# ATMega328PCBBoard.net
KiCad netlist of a schematic drawn in EAGLE
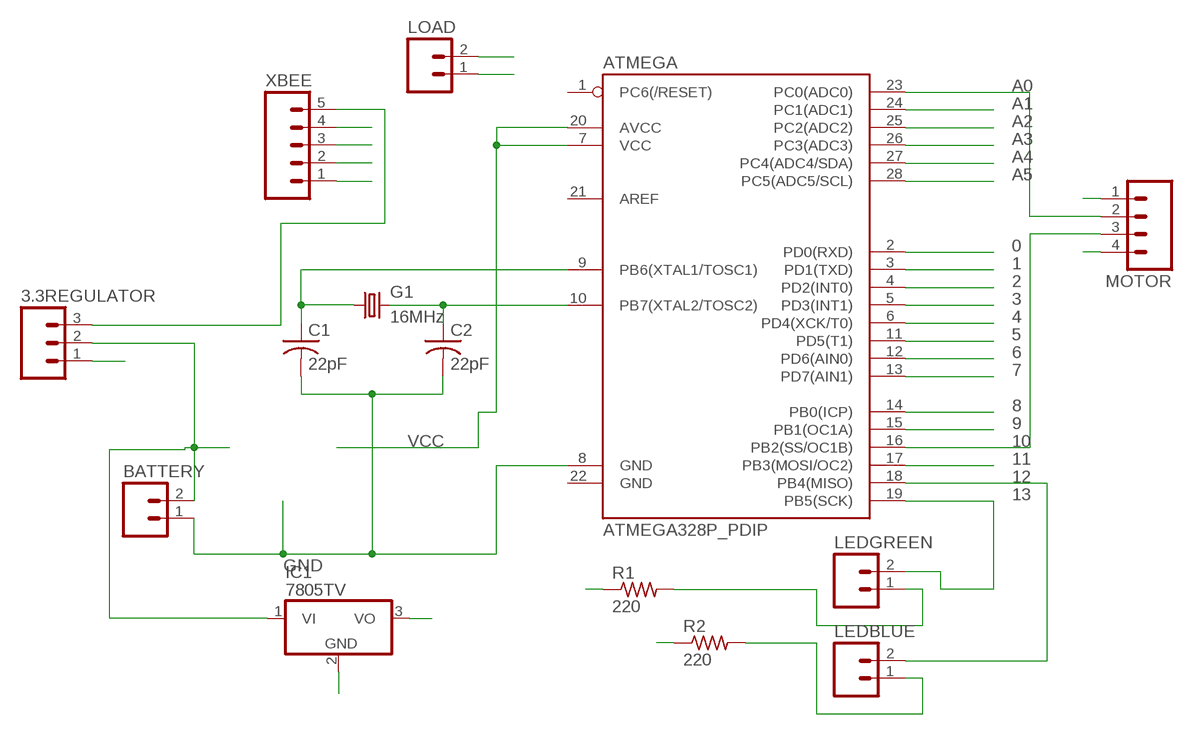
[diagram p0: schematic, sheet 1]

(export (version "E")
  (design (tool "Eeschema 10.0.6"))
  (components
    (comp (ref "3.3REGULATOR")
      (value "M03JST-PTH-VERT")
      (footprint "eagle-import:JST-3-PTH-VERT")
      (libsource (lib "eagle-import") (part "M03JST-PTH-VERT"))
    )
    (comp (ref "ATMEGA")
      (value "ATMEGA328P_PDIP")
      (footprint "eagle-import:DIL28-3")
      (libsource (lib "eagle-import") (part "ATMEGA328P_PDIP"))
    )
    (comp (ref "BATTERY")
      (value "M02JST-PTH-VERT")
      (footprint "eagle-import:JST-2-PTH-VERT")
      (libsource (lib "eagle-import") (part "M02JST-PTH-VERT"))
    )
    (comp (ref "C1")
      (value "22pF")
      (footprint "eagle-import:C050-025X075")
      (libsource (lib "eagle-import") (part "C-US050-025X075"))
    )
    (comp (ref "C2")
      (value "22pF")
      (footprint "eagle-import:C050-025X075")
      (libsource (lib "eagle-import") (part "C-US050-025X075"))
    )
    (comp (ref "G1")
      (value "16MHz")
      (footprint "eagle-import:HC49US")
      (libsource (lib "eagle-import") (part "CRYSTALHC49US"))
    )
    (comp (ref "IC1")
      (value "7805TV")
      (footprint "eagle-import:TO220V")
      (libsource (lib "eagle-import") (part "78TV05"))
    )
    (comp (ref "LEDBLUE")
      (value "M02JST-PTH-VERT")
      (footprint "eagle-import:JST-2-PTH-VERT")
      (libsource (lib "eagle-import") (part "M02JST-PTH-VERT"))
    )
    (comp (ref "LEDGREEN")
      (value "M02JST-PTH-VERT")
      (footprint "eagle-import:JST-2-PTH-VERT")
      (libsource (lib "eagle-import") (part "M02JST-PTH-VERT"))
    )
    (comp (ref "LOAD")
      (value "M02JST-PTH-VERT")
      (footprint "eagle-import:JST-2-PTH-VERT")
      (libsource (lib "eagle-import") (part "M02JST-PTH-VERT"))
    )
    (comp (ref "MOTOR")
      (value "M04JST")
      (footprint "eagle-import:1X04-1.5MM_JST")
      (libsource (lib "eagle-import") (part "M04JST"))
    )
    (comp (ref "R1")
      (value "220")
      (footprint "eagle-import:0207_2V")
      (libsource (lib "eagle-import") (part "R-US_0207/2V"))
    )
    (comp (ref "R2")
      (value "220")
      (footprint "eagle-import:0207_2V")
      (libsource (lib "eagle-import") (part "R-US_0207/2V"))
    )
    (comp (ref "XBEE")
      (value "M05JST-VERT")
      (footprint "eagle-import:JST-5-PTH-VERT")
      (libsource (lib "eagle-import") (part "M05JST-VERT"))
    )
  )
  (nets
    (net (code "1") (name "/0") (class "Default")
      (node (ref "ATMEGA") (pin "2") (pinfunction "PD0(RXD)_2") (pintype "bidirectional"))
      (node (ref "LOAD") (pin "1") (pinfunction "1_1") (pintype "passive"))
      (node (ref "XBEE") (pin "4") (pinfunction "4_4") (pintype "passive"))
    )
    (net (code "2") (name "/1") (class "Default")
      (node (ref "ATMEGA") (pin "3") (pinfunction "PD1(TXD)_3") (pintype "bidirectional"))
      (node (ref "LOAD") (pin "2") (pinfunction "2_2") (pintype "passive"))
      (node (ref "XBEE") (pin "3") (pinfunction "3_3") (pintype "passive"))
    )
    (net (code "3") (name "/7") (class "Default")
      (node (ref "ATMEGA") (pin "13") (pinfunction "PD7(AIN1)_13") (pintype "bidirectional"))
      (node (ref "XBEE") (pin "1") (pinfunction "1_1") (pintype "passive"))
    )
    (net (code "4") (name "/GND") (class "Default")
      (node (ref "3.3REGULATOR") (pin "1") (pinfunction "1_1") (pintype "passive"))
      (node (ref "ATMEGA") (pin "8") (pinfunction "GND_8") (pintype "bidirectional"))
      (node (ref "BATTERY") (pin "1") (pinfunction "1_1") (pintype "passive"))
      (node (ref "C1") (pin "2") (pinfunction "2_2") (pintype "passive"))
      (node (ref "C2") (pin "2") (pinfunction "2_2") (pintype "passive"))
      (node (ref "IC1") (pin "2") (pinfunction "GND_2") (pintype "passive"))
      (node (ref "MOTOR") (pin "4") (pinfunction "4_4") (pintype "passive"))
      (node (ref "R1") (pin "1") (pinfunction "1_1") (pintype "passive"))
      (node (ref "R2") (pin "1") (pinfunction "1_1") (pintype "passive"))
      (node (ref "XBEE") (pin "2") (pinfunction "2_2") (pintype "passive"))
    )
    (net (code "5") (name "/VCC") (class "Default")
      (node (ref "ATMEGA") (pin "20") (pinfunction "AVCC_20") (pintype "bidirectional"))
      (node (ref "ATMEGA") (pin "7") (pinfunction "VCC_7") (pintype "bidirectional"))
      (node (ref "IC1") (pin "3") (pinfunction "VO_3") (pintype "passive"))
      (node (ref "MOTOR") (pin "1") (pinfunction "1_1") (pintype "passive"))
    )
    (net (code "6") (name "Net-(3.3REGULATOR-Pad3)") (class "Default")
      (node (ref "3.3REGULATOR") (pin "3") (pinfunction "3_3") (pintype "passive"))
      (node (ref "XBEE") (pin "5") (pinfunction "5_5") (pintype "passive"))
    )
    (net (code "7") (name "Net-(ATMEGA-PB2(SS{slash}OC1B))") (class "Default")
      (node (ref "ATMEGA") (pin "16") (pinfunction "PB2(SS/OC1B)_16") (pintype "bidirectional"))
      (node (ref "MOTOR") (pin "3") (pinfunction "3_3") (pintype "passive"))
    )
    (net (code "8") (name "Net-(ATMEGA-PB4(MISO))") (class "Default")
      (node (ref "ATMEGA") (pin "18") (pinfunction "PB4(MISO)_18") (pintype "bidirectional"))
      (node (ref "LEDBLUE") (pin "2") (pinfunction "2_2") (pintype "passive"))
    )
    (net (code "9") (name "Net-(ATMEGA-PB5(SCK))") (class "Default")
      (node (ref "ATMEGA") (pin "19") (pinfunction "PB5(SCK)_19") (pintype "bidirectional"))
      (node (ref "LEDGREEN") (pin "2") (pinfunction "2_2") (pintype "passive"))
    )
    (net (code "10") (name "Net-(ATMEGA-PB6(XTAL1{slash}TOSC1))") (class "Default")
      (node (ref "ATMEGA") (pin "9") (pinfunction "PB6(XTAL1/TOSC1)_9") (pintype "bidirectional"))
      (node (ref "C1") (pin "1") (pinfunction "1_1") (pintype "passive"))
      (node (ref "G1") (pin "1") (pinfunction "1_1") (pintype "passive"))
    )
    (net (code "11") (name "Net-(ATMEGA-PB7(XTAL2{slash}TOSC2))") (class "Default")
      (node (ref "ATMEGA") (pin "10") (pinfunction "PB7(XTAL2/TOSC2)_10") (pintype "bidirectional"))
      (node (ref "C2") (pin "1") (pinfunction "1_1") (pintype "passive"))
      (node (ref "G1") (pin "2") (pinfunction "2_2") (pintype "passive"))
    )
    (net (code "12") (name "Net-(ATMEGA-PC0(ADC0))") (class "Default")
      (node (ref "ATMEGA") (pin "23") (pinfunction "PC0(ADC0)_23") (pintype "bidirectional"))
      (node (ref "MOTOR") (pin "2") (pinfunction "2_2") (pintype "passive"))
    )
    (net (code "13") (name "Net-(IC1-VI)") (class "Default")
      (node (ref "3.3REGULATOR") (pin "2") (pinfunction "2_2") (pintype "passive"))
      (node (ref "BATTERY") (pin "2") (pinfunction "2_2") (pintype "passive"))
      (node (ref "IC1") (pin "1") (pinfunction "VI_1") (pintype "input"))
    )
    (net (code "14") (name "Net-(LEDBLUE-Pad1)") (class "Default")
      (node (ref "LEDBLUE") (pin "1") (pinfunction "1_1") (pintype "passive"))
      (node (ref "R2") (pin "2") (pinfunction "2_2") (pintype "passive"))
    )
    (net (code "15") (name "Net-(LEDGREEN-Pad1)") (class "Default")
      (node (ref "LEDGREEN") (pin "1") (pinfunction "1_1") (pintype "passive"))
      (node (ref "R1") (pin "2") (pinfunction "2_2") (pintype "passive"))
    )
    (net (code "16") (name "unconnected-(ATMEGA-AREF-Pad21)") (class "Default")
      (node (ref "ATMEGA") (pin "21") (pinfunction "AREF_21") (pintype "bidirectional"))
    )
    (net (code "17") (name "unconnected-(ATMEGA-GND-Pad22)") (class "Default")
      (node (ref "ATMEGA") (pin "22") (pinfunction "GND_22") (pintype "bidirectional"))
    )
    (net (code "18") (name "unconnected-(ATMEGA-PB0(ICP)-Pad14)") (class "Default")
      (node (ref "ATMEGA") (pin "14") (pinfunction "PB0(ICP)_14") (pintype "bidirectional"))
    )
    (net (code "19") (name "unconnected-(ATMEGA-PB1(OC1A)-Pad15)") (class "Default")
      (node (ref "ATMEGA") (pin "15") (pinfunction "PB1(OC1A)_15") (pintype "bidirectional"))
    )
    (net (code "20") (name "unconnected-(ATMEGA-PB3(MOSI{slash}OC2)-Pad17)") (class "Default")
      (node (ref "ATMEGA") (pin "17") (pinfunction "PB3(MOSI/OC2)_17") (pintype "bidirectional"))
    )
    (net (code "21") (name "unconnected-(ATMEGA-PC1(ADC1)-Pad24)") (class "Default")
      (node (ref "ATMEGA") (pin "24") (pinfunction "PC1(ADC1)_24") (pintype "bidirectional"))
    )
    (net (code "22") (name "unconnected-(ATMEGA-PC2(ADC2)-Pad25)") (class "Default")
      (node (ref "ATMEGA") (pin "25") (pinfunction "PC2(ADC2)_25") (pintype "bidirectional"))
    )
    (net (code "23") (name "unconnected-(ATMEGA-PC3(ADC3)-Pad26)") (class "Default")
      (node (ref "ATMEGA") (pin "26") (pinfunction "PC3(ADC3)_26") (pintype "bidirectional"))
    )
    (net (code "24") (name "unconnected-(ATMEGA-PC4(ADC4{slash}SDA)-Pad27)") (class "Default")
      (node (ref "ATMEGA") (pin "27") (pinfunction "PC4(ADC4/SDA)_27") (pintype "bidirectional"))
    )
    (net (code "25") (name "unconnected-(ATMEGA-PC5(ADC5{slash}SCL)-Pad28)") (class "Default")
      (node (ref "ATMEGA") (pin "28") (pinfunction "PC5(ADC5/SCL)_28") (pintype "bidirectional"))
    )
    (net (code "26") (name "unconnected-(ATMEGA-PC6({slash}RESET)-Pad1)") (class "Default")
      (node (ref "ATMEGA") (pin "1") (pinfunction "PC6(/RESET)_1") (pintype "bidirectional"))
    )
    (net (code "27") (name "unconnected-(ATMEGA-PD2(INT0)-Pad4)") (class "Default")
      (node (ref "ATMEGA") (pin "4") (pinfunction "PD2(INT0)_4") (pintype "bidirectional"))
    )
    (net (code "28") (name "unconnected-(ATMEGA-PD3(INT1)-Pad5)") (class "Default")
      (node (ref "ATMEGA") (pin "5") (pinfunction "PD3(INT1)_5") (pintype "bidirectional"))
    )
    (net (code "29") (name "unconnected-(ATMEGA-PD4(XCK{slash}T0)-Pad6)") (class "Default")
      (node (ref "ATMEGA") (pin "6") (pinfunction "PD4(XCK/T0)_6") (pintype "bidirectional"))
    )
    (net (code "30") (name "unconnected-(ATMEGA-PD5(T1)-Pad11)") (class "Default")
      (node (ref "ATMEGA") (pin "11") (pinfunction "PD5(T1)_11") (pintype "bidirectional"))
    )
    (net (code "31") (name "unconnected-(ATMEGA-PD6(AIN0)-Pad12)") (class "Default")
      (node (ref "ATMEGA") (pin "12") (pinfunction "PD6(AIN0)_12") (pintype "bidirectional"))
    )
  )
)
